# Microcontrollers.net
KiCad netlist of a schematic drawn in Altium Designer
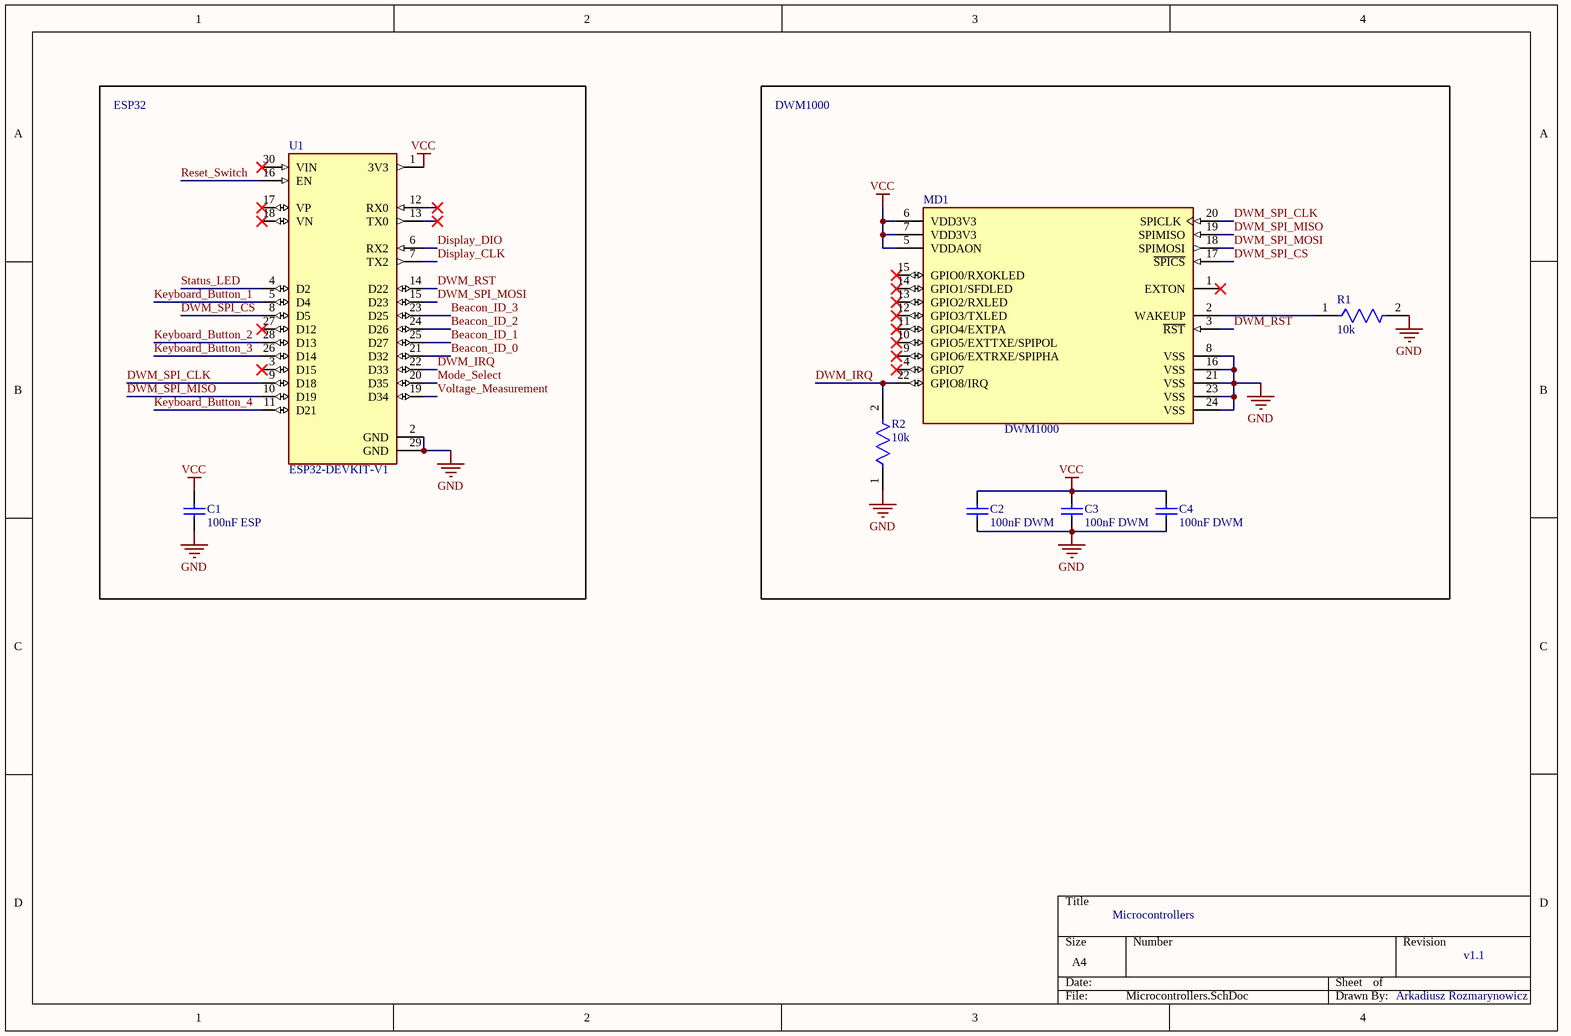
[diagram p0: Microcontrollers.SchDoc]

(export (version "E")
  (design (tool "Eeschema 10.0.6"))
  (components
    (comp (ref "C1")
      (value "100nF ESP")
      (footprint "CAPC2013X145X48NL20T23")
      (fields (field (name "PART NUMBER") "VJ0805Y104KXAMR") (field (name "MANUFACTURER") "Vitramon"))
      (libsource (lib "Altium Content Vault") (part "CAP"))
    )
    (comp (ref "C2")
      (value "100nF DWM")
      (footprint "CAPC2013X145X48NL20T23")
      (fields (field (name "PART NUMBER") "VJ0805Y104KXAMR") (field (name "MANUFACTURER") "Vitramon"))
      (libsource (lib "Altium Content Vault") (part "CAP"))
    )
    (comp (ref "C3")
      (value "100nF DWM")
      (footprint "CAPC2013X145X48NL20T23")
      (fields (field (name "PART NUMBER") "VJ0805Y104KXAMR") (field (name "MANUFACTURER") "Vitramon"))
      (libsource (lib "Altium Content Vault") (part "CAP"))
    )
    (comp (ref "C4")
      (value "100nF DWM")
      (footprint "CAPC2013X145X48NL20T23")
      (fields (field (name "PART NUMBER") "VJ0805Y104KXAMR") (field (name "MANUFACTURER") "Vitramon"))
      (libsource (lib "Altium Content Vault") (part "CAP"))
    )
    (comp (ref "MD1")
      (value "DWM1000")
      (footprint "FP-DWM1000-MFG")
      (description "RX TXRX MODULE 802.15.4 CHIP SMD")
      (libsource (lib "Altium Content Vault") (part "f696d20320cfac42d99354fdc9dc59a"))
    )
    (comp (ref "R1")
      (value "10k")
      (footprint "FP-CRGCQ0805-IPC_C")
      (description "CRGCQ0805 10KΩ 0.125W ±100ppm/°C 5% 150V")
      (fields
        (field (name "TOLERANCE") "0.05")
        (field (name "OCTOPART") "https://octopart.com/crgcq0805j100k-te+connectivity-91018199")
      )
      (libsource (lib "Altium Content Vault") (part "1029c3af85768c4190bb7ad29bc67b5"))
    )
    (comp (ref "R2")
      (value "10k")
      (footprint "FP-CRGCQ0805-IPC_C")
      (description "CRGCQ0805 10KΩ 0.125W ±100ppm/°C 5% 150V")
      (fields
        (field (name "TOLERANCE") "0.05")
        (field (name "OCTOPART") "https://octopart.com/crgcq0805j100k-te+connectivity-91018199")
      )
      (libsource (lib "Altium Content Vault") (part "1029c3af85768c4190bb7ad29bc67b5"))
    )
    (comp (ref "U1")
      (value "ESP32-DEVKIT-V1")
      (footprint "MODULE_ESP32_DEVKIT_V1")
      (fields (field (name "MF") "Do it"))
      (libsource (lib "ESP32-DEVKIT-V1") (part "ESP32-DEVKIT-V1"))
    )
  )
  (nets
    (net (code "1") (name "/Beacon_ID_0") (class "Default")
      (node (ref "U1") (pin "21") (pinfunction "D32_21") (pintype "bidirectional"))
    )
    (net (code "2") (name "/Beacon_ID_1") (class "Default")
      (node (ref "U1") (pin "25") (pinfunction "D27_25") (pintype "bidirectional"))
    )
    (net (code "3") (name "/Beacon_ID_2") (class "Default")
      (node (ref "U1") (pin "24") (pinfunction "D26_24") (pintype "bidirectional"))
    )
    (net (code "4") (name "/Beacon_ID_3") (class "Default")
      (node (ref "U1") (pin "23") (pinfunction "D25_23") (pintype "bidirectional"))
    )
    (net (code "5") (name "/DWM_IRQ") (class "Default")
      (node (ref "MD1") (pin "22") (pinfunction "GPIO8/IRQ_22") (pintype "bidirectional"))
      (node (ref "R2") (pin "2") (pinfunction "2_2") (pintype "passive"))
      (node (ref "U1") (pin "22") (pinfunction "D33_22") (pintype "bidirectional"))
    )
    (net (code "6") (name "/DWM_RST") (class "Default")
      (node (ref "MD1") (pin "3") (pinfunction "~{RST}_3") (pintype "input"))
      (node (ref "U1") (pin "14") (pinfunction "D22_14") (pintype "bidirectional"))
    )
    (net (code "7") (name "/DWM_SPI_CLK") (class "Default")
      (node (ref "MD1") (pin "20") (pinfunction "SPICLK_20") (pintype "input"))
      (node (ref "U1") (pin "9") (pinfunction "D18_9") (pintype "bidirectional"))
    )
    (net (code "8") (name "/DWM_SPI_CS") (class "Default")
      (node (ref "MD1") (pin "17") (pinfunction "~{SPICS}_17") (pintype "input"))
      (node (ref "U1") (pin "8") (pinfunction "D5_8") (pintype "bidirectional"))
    )
    (net (code "9") (name "/DWM_SPI_MISO") (class "Default")
      (node (ref "MD1") (pin "19") (pinfunction "SPIMISO_19") (pintype "input"))
      (node (ref "U1") (pin "10") (pinfunction "D19_10") (pintype "bidirectional"))
    )
    (net (code "10") (name "/DWM_SPI_MOSI") (class "Default")
      (node (ref "MD1") (pin "18") (pinfunction "SPIMOSI_18") (pintype "output"))
      (node (ref "U1") (pin "15") (pinfunction "D23_15") (pintype "bidirectional"))
    )
    (net (code "11") (name "/Display_CLK") (class "Default")
      (node (ref "U1") (pin "7") (pinfunction "TX2_7") (pintype "output"))
    )
    (net (code "12") (name "/Display_DIO") (class "Default")
      (node (ref "U1") (pin "6") (pinfunction "RX2_6") (pintype "input"))
    )
    (net (code "13") (name "/Keyboard_Button_1") (class "Default")
      (node (ref "U1") (pin "5") (pinfunction "D4_5") (pintype "bidirectional"))
    )
    (net (code "14") (name "/Keyboard_Button_2") (class "Default")
      (node (ref "U1") (pin "28") (pinfunction "D13_28") (pintype "bidirectional"))
    )
    (net (code "15") (name "/Keyboard_Button_3") (class "Default")
      (node (ref "U1") (pin "26") (pinfunction "D14_26") (pintype "bidirectional"))
    )
    (net (code "16") (name "/Keyboard_Button_4") (class "Default")
      (node (ref "U1") (pin "11") (pinfunction "D21_11") (pintype "bidirectional"))
    )
    (net (code "17") (name "/Mode_Select") (class "Default")
      (node (ref "U1") (pin "20") (pinfunction "D35_20") (pintype "bidirectional"))
    )
    (net (code "18") (name "/Reset_Switch") (class "Default")
      (node (ref "U1") (pin "16") (pinfunction "EN_16") (pintype "input"))
    )
    (net (code "19") (name "/Status_LED") (class "Default")
      (node (ref "U1") (pin "4") (pinfunction "D2_4") (pintype "bidirectional"))
    )
    (net (code "20") (name "/Voltage_Measurement") (class "Default")
      (node (ref "U1") (pin "19") (pinfunction "D34_19") (pintype "bidirectional"))
    )
    (net (code "21") (name "GND") (class "Default")
      (node (ref "C1") (pin "1") (pinfunction "1_1") (pintype "passive"))
      (node (ref "C2") (pin "1") (pinfunction "1_1") (pintype "passive"))
      (node (ref "C3") (pin "1") (pinfunction "1_1") (pintype "passive"))
      (node (ref "C4") (pin "1") (pinfunction "1_1") (pintype "passive"))
      (node (ref "MD1") (pin "16") (pinfunction "VSS_16") (pintype "power_in"))
      (node (ref "MD1") (pin "21") (pinfunction "VSS_21") (pintype "power_in"))
      (node (ref "MD1") (pin "23") (pinfunction "VSS_23") (pintype "power_in"))
      (node (ref "MD1") (pin "24") (pinfunction "VSS_24") (pintype "power_in"))
      (node (ref "MD1") (pin "8") (pinfunction "VSS_8") (pintype "power_in"))
      (node (ref "R1") (pin "2") (pinfunction "2_2") (pintype "passive"))
      (node (ref "R2") (pin "1") (pinfunction "1_1") (pintype "passive"))
      (node (ref "U1") (pin "2") (pinfunction "GND_2") (pintype "power_in"))
      (node (ref "U1") (pin "29") (pinfunction "GND_29") (pintype "power_in"))
    )
    (net (code "22") (name "Net-(MD1-WAKEUP)") (class "Default")
      (node (ref "MD1") (pin "2") (pinfunction "WAKEUP_2") (pintype "passive"))
      (node (ref "R1") (pin "1") (pinfunction "1_1") (pintype "passive"))
    )
    (net (code "23") (name "VCC") (class "Default")
      (node (ref "C1") (pin "2") (pinfunction "2_2") (pintype "passive"))
      (node (ref "C2") (pin "2") (pinfunction "2_2") (pintype "passive"))
      (node (ref "C3") (pin "2") (pinfunction "2_2") (pintype "passive"))
      (node (ref "C4") (pin "2") (pinfunction "2_2") (pintype "passive"))
      (node (ref "MD1") (pin "5") (pinfunction "VDDAON_5") (pintype "power_in"))
      (node (ref "MD1") (pin "6") (pinfunction "VDD3V3_6") (pintype "power_in"))
      (node (ref "MD1") (pin "7") (pinfunction "VDD3V3_7") (pintype "power_in"))
      (node (ref "U1") (pin "1") (pinfunction "3V3_1") (pintype "output"))
    )
    (net (code "24") (name "unconnected-(MD1-EXTON-Pad1)") (class "Default")
      (node (ref "MD1") (pin "1") (pinfunction "EXTON_1") (pintype "passive+no_connect"))
    )
    (net (code "25") (name "unconnected-(MD1-GPIO0{slash}RXOKLED-Pad15)") (class "Default")
      (node (ref "MD1") (pin "15") (pinfunction "GPIO0/RXOKLED_15") (pintype "bidirectional+no_connect"))
    )
    (net (code "26") (name "unconnected-(MD1-GPIO1{slash}SFDLED-Pad14)") (class "Default")
      (node (ref "MD1") (pin "14") (pinfunction "GPIO1/SFDLED_14") (pintype "bidirectional+no_connect"))
    )
    (net (code "27") (name "unconnected-(MD1-GPIO2{slash}RXLED-Pad13)") (class "Default")
      (node (ref "MD1") (pin "13") (pinfunction "GPIO2/RXLED_13") (pintype "bidirectional+no_connect"))
    )
    (net (code "28") (name "unconnected-(MD1-GPIO3{slash}TXLED-Pad12)") (class "Default")
      (node (ref "MD1") (pin "12") (pinfunction "GPIO3/TXLED_12") (pintype "bidirectional+no_connect"))
    )
    (net (code "29") (name "unconnected-(MD1-GPIO4{slash}EXTPA-Pad11)") (class "Default")
      (node (ref "MD1") (pin "11") (pinfunction "GPIO4/EXTPA_11") (pintype "bidirectional+no_connect"))
    )
    (net (code "30") (name "unconnected-(MD1-GPIO5{slash}EXTTXE{slash}SPIPOL-Pad10)") (class "Default")
      (node (ref "MD1") (pin "10") (pinfunction "GPIO5/EXTTXE/SPIPOL_10") (pintype "bidirectional+no_connect"))
    )
    (net (code "31") (name "unconnected-(MD1-GPIO6{slash}EXTRXE{slash}SPIPHA-Pad9)") (class "Default")
      (node (ref "MD1") (pin "9") (pinfunction "GPIO6/EXTRXE/SPIPHA_9") (pintype "bidirectional+no_connect"))
    )
    (net (code "32") (name "unconnected-(MD1-GPIO7-Pad4)") (class "Default")
      (node (ref "MD1") (pin "4") (pinfunction "GPIO7_4") (pintype "bidirectional+no_connect"))
    )
    (net (code "33") (name "unconnected-(U1-D12-Pad27)") (class "Default")
      (node (ref "U1") (pin "27") (pinfunction "D12_27") (pintype "bidirectional+no_connect"))
    )
    (net (code "34") (name "unconnected-(U1-D15-Pad3)") (class "Default")
      (node (ref "U1") (pin "3") (pinfunction "D15_3") (pintype "bidirectional+no_connect"))
    )
    (net (code "35") (name "unconnected-(U1-RX0-Pad12)") (class "Default")
      (node (ref "U1") (pin "12") (pinfunction "RX0_12") (pintype "input+no_connect"))
    )
    (net (code "36") (name "unconnected-(U1-TX0-Pad13)") (class "Default")
      (node (ref "U1") (pin "13") (pinfunction "TX0_13") (pintype "output+no_connect"))
    )
    (net (code "37") (name "unconnected-(U1-VIN-Pad30)") (class "Default")
      (node (ref "U1") (pin "30") (pinfunction "VIN_30") (pintype "input+no_connect"))
    )
    (net (code "38") (name "unconnected-(U1-VN-Pad18)") (class "Default")
      (node (ref "U1") (pin "18") (pinfunction "VN_18") (pintype "bidirectional+no_connect"))
    )
    (net (code "39") (name "unconnected-(U1-VP-Pad17)") (class "Default")
      (node (ref "U1") (pin "17") (pinfunction "VP_17") (pintype "bidirectional+no_connect"))
    )
  )
)
